# ARM_EURO_Platine5.net
KiCad netlist of a schematic drawn in Altium Designer
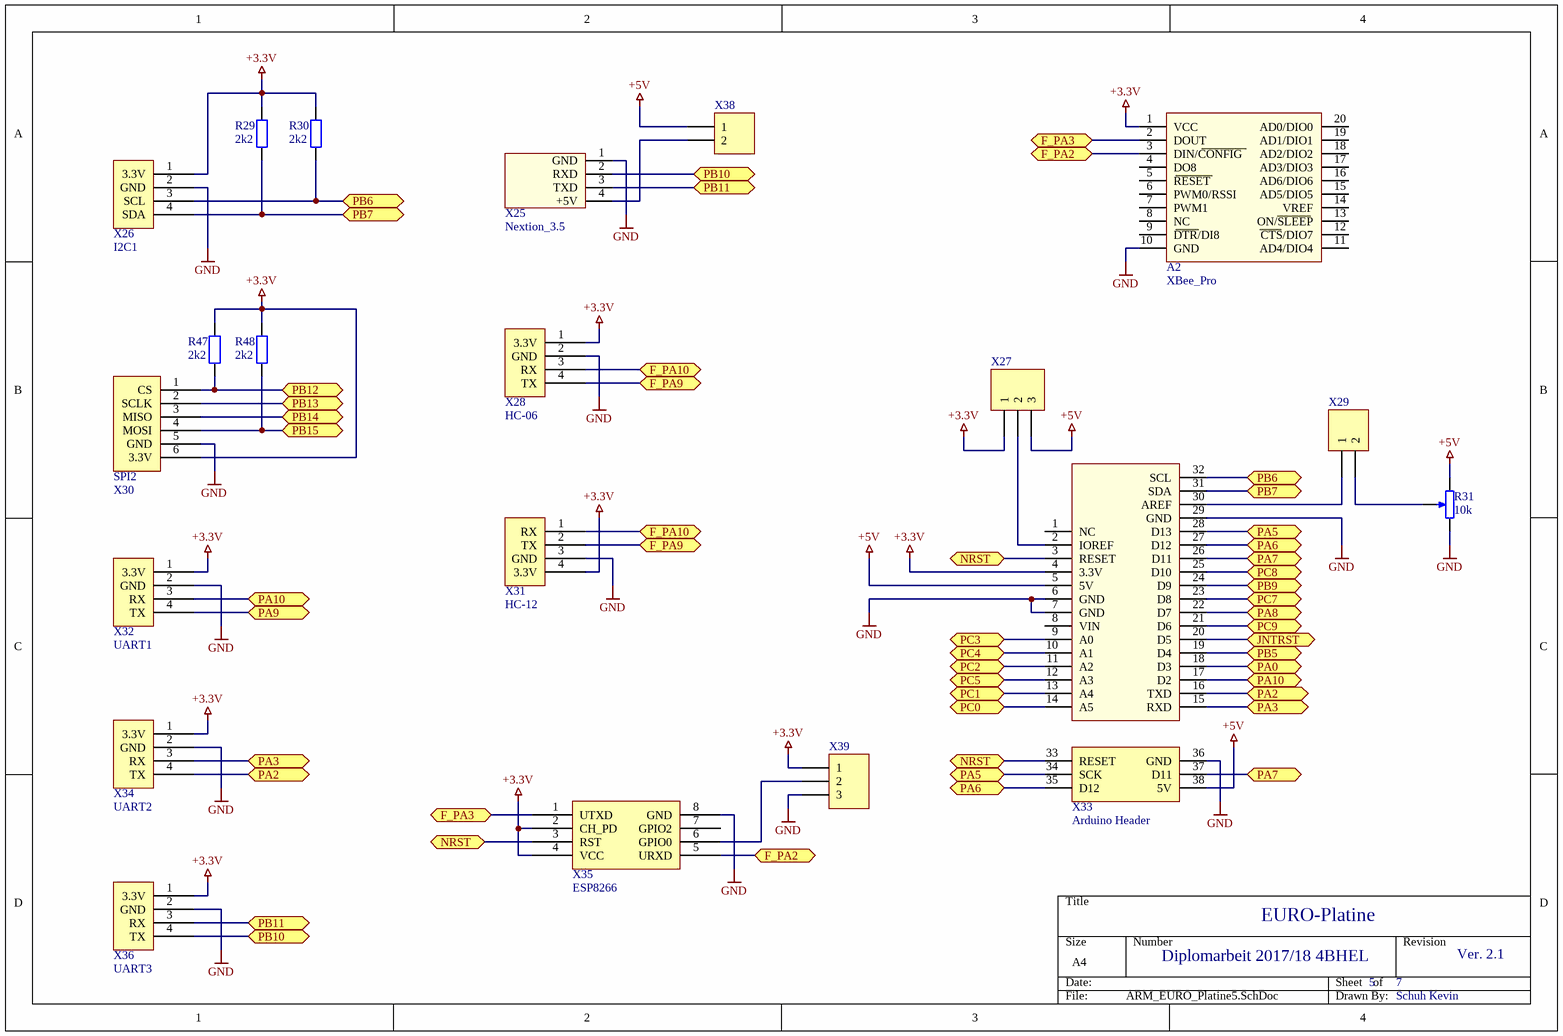
[diagram p0: ARM_EURO_Platine5.SchDoc]

(export (version "E")
  (design (tool "Eeschema 10.0.6"))
  (components
    (comp (ref "A2")
      (value "XBee_Pro")
      (footprint "XBee_Pro")
      (description "Funkmodul")
      (libsource (lib "ARM_Libary_EURO") (part "XBee_Pro"))
    )
    (comp (ref "R29")
      (value "2k2")
      (footprint "0805_Res")
      (description "Resistor")
      (fields (field (name "Comment") "Res_SMD") (field (name "PUBLISHER") "Altium Limited"))
      (libsource (lib "ARM_Libary_EURO") (part "Res_SMD"))
    )
    (comp (ref "R30")
      (value "2k2")
      (footprint "0805_Res")
      (description "Resistor")
      (fields (field (name "Comment") "Res_SMD") (field (name "PUBLISHER") "Altium Limited"))
      (libsource (lib "ARM_Libary_EURO") (part "Res_SMD"))
    )
    (comp (ref "R31")
      (value "10k")
      (footprint "Potentiometer")
      (description "Potentiometer")
      (fields (field (name "Comment") "RPot") (field (name "PUBLISHER") "Altium Limited"))
      (libsource (lib "ARM_Libary_EURO") (part "RPot"))
    )
    (comp (ref "R47")
      (value "2k2")
      (footprint "0805_Res")
      (description "Resistor")
      (fields (field (name "Comment") "Res_SMD") (field (name "PUBLISHER") "Altium Limited"))
      (libsource (lib "ARM_Libary_EURO") (part "Res_SMD"))
    )
    (comp (ref "R48")
      (value "2k2")
      (footprint "0805_Res")
      (description "Resistor")
      (fields (field (name "Comment") "Res_SMD") (field (name "PUBLISHER") "Altium Limited"))
      (libsource (lib "ARM_Libary_EURO") (part "Res_SMD"))
    )
    (comp (ref "X25")
      (value "Nextion_3.5")
      (footprint "Nextion_3.5")
      (libsource (lib "ARM_Libary_EURO") (part "Nextion_3.5"))
    )
    (comp (ref "X26")
      (value "I2C1")
      (footprint "I2C_Interface")
      (description "Stiftleiste 4Pol")
      (libsource (lib "ARM_Libary_EURO") (part "I2C_Interface"))
    )
    (comp (ref "X27")
      (value "Header_3")
      (footprint "HDR1X3")
      (description "Header, 3-Pin")
      (fields (field (name "PUBLISHER") "Altium Limited"))
      (libsource (lib "ARM_Libary_EURO") (part "Header_3"))
    )
    (comp (ref "X28")
      (value "HC-06")
      (footprint "HC_06")
      (description "Stiftleiste 4Pol")
      (libsource (lib "ARM_Libary_EURO") (part "HC_06"))
    )
    (comp (ref "X29")
      (value "Header")
      (footprint "HDR1X2")
      (description "Header, 2-Pin")
      (fields (field (name "PUBLISHER") "Altium Limited"))
      (libsource (lib "") (part "Header_2_1"))
    )
    (comp (ref "X30")
      (value "SPI2")
      (footprint "SPI_Interface")
      (description "Stiftleiste 6Pol")
      (libsource (lib "ARM_Libary_EURO") (part "SPI_Interface"))
    )
    (comp (ref "X31") (value "HC-12") (footprint "HC_12") (libsource (lib "ARM_Libary_EURO") (part "HC_12")))
    (comp (ref "X32")
      (value "UART1")
      (footprint "UART_Interface")
      (description "Stiftleiste 4Pol")
      (libsource (lib "ARM_Libary_EURO") (part "UART_Interface"))
    )
    (comp (ref "X33")
      (value "Arduino Header")
      (footprint "Arduino")
      (libsource (lib "ARM_Libary_EURO") (part "Arduino"))
    )
    (comp (ref "X34")
      (value "UART2")
      (footprint "UART_Interface")
      (description "Stiftleiste 4Pol")
      (libsource (lib "ARM_Libary_EURO") (part "UART_Interface"))
    )
    (comp (ref "X35")
      (value "ESP8266")
      (footprint "ESP8266")
      (description "W-LAN Modul")
      (libsource (lib "ARM_Libary_EURO") (part "ESP8266"))
    )
    (comp (ref "X36")
      (value "UART3")
      (footprint "UART_Interface")
      (description "Stiftleiste 4Pol")
      (libsource (lib "ARM_Libary_EURO") (part "UART_Interface"))
    )
    (comp (ref "X38")
      (value "Header")
      (footprint "HDR1X2")
      (description "Header, 2-Pin")
      (fields (field (name "PUBLISHER") "Altium Limited"))
      (libsource (lib "ARM_Libary_EURO") (part "Header_2"))
    )
    (comp (ref "X39")
      (value "Header_3")
      (footprint "HDR1X3")
      (description "Header, 3-Pin")
      (fields (field (name "PUBLISHER") "Altium Limited"))
      (libsource (lib "") (part "Header_3_1"))
    )
  )
  (nets
    (net (code "1") (name "+3.3V") (class "Default")
      (node (ref "A2") (pin "1") (pinfunction "VCC_1") (pintype "passive"))
      (node (ref "R29") (pin "2") (pinfunction "2_2") (pintype "passive"))
      (node (ref "R30") (pin "2") (pinfunction "2_2") (pintype "passive"))
      (node (ref "R47") (pin "2") (pinfunction "2_2") (pintype "passive"))
      (node (ref "R48") (pin "2") (pinfunction "2_2") (pintype "passive"))
      (node (ref "X26") (pin "1") (pinfunction "3.3V_1") (pintype "passive"))
      (node (ref "X27") (pin "1") (pinfunction "1_1") (pintype "passive"))
      (node (ref "X28") (pin "1") (pinfunction "3.3V_1") (pintype "passive"))
      (node (ref "X30") (pin "6") (pinfunction "3.3V_6") (pintype "passive"))
      (node (ref "X31") (pin "4") (pinfunction "3.3V_4") (pintype "passive"))
      (node (ref "X32") (pin "1") (pinfunction "3.3V_1") (pintype "passive"))
      (node (ref "X33") (pin "4") (pinfunction "3.3V_4") (pintype "passive"))
      (node (ref "X34") (pin "1") (pinfunction "3.3V_1") (pintype "passive"))
      (node (ref "X35") (pin "2") (pinfunction "CH_PD_2") (pintype "passive"))
      (node (ref "X35") (pin "4") (pinfunction "VCC_4") (pintype "passive"))
      (node (ref "X36") (pin "1") (pinfunction "3.3V_1") (pintype "passive"))
      (node (ref "X39") (pin "1") (pinfunction "1_1") (pintype "passive"))
    )
    (net (code "2") (name "+5V") (class "Default")
      (node (ref "R31") (pin "1") (pinfunction "TOP_1") (pintype "passive"))
      (node (ref "X27") (pin "3") (pinfunction "3_3") (pintype "passive"))
      (node (ref "X33") (pin "38") (pinfunction "5V_38") (pintype "passive"))
      (node (ref "X33") (pin "5") (pinfunction "5V_5") (pintype "passive"))
      (node (ref "X38") (pin "1") (pinfunction "1_1") (pintype "passive"))
    )
    (net (code "3") (name "/F_PA2") (class "Default")
      (node (ref "A2") (pin "3") (pinfunction "DIN/CONFIG_3") (pintype "passive"))
      (node (ref "X35") (pin "5") (pinfunction "URXD_5") (pintype "passive"))
    )
    (net (code "4") (name "/F_PA3") (class "Default")
      (node (ref "A2") (pin "2") (pinfunction "DOUT_2") (pintype "passive"))
      (node (ref "X35") (pin "1") (pinfunction "UTXD_1") (pintype "passive"))
    )
    (net (code "5") (name "/F_PA9") (class "Default")
      (node (ref "X28") (pin "4") (pinfunction "TX_4") (pintype "passive"))
      (node (ref "X31") (pin "2") (pinfunction "TX_2") (pintype "passive"))
    )
    (net (code "6") (name "/F_PA10") (class "Default")
      (node (ref "X28") (pin "3") (pinfunction "RX_3") (pintype "passive"))
      (node (ref "X31") (pin "1") (pinfunction "RX_1") (pintype "passive"))
    )
    (net (code "7") (name "/JNTRST") (class "Default")
      (node (ref "X33") (pin "20") (pinfunction "D5_20") (pintype "passive"))
    )
    (net (code "8") (name "/NRST") (class "Default")
      (node (ref "X33") (pin "3") (pinfunction "RESET_3") (pintype "passive"))
      (node (ref "X33") (pin "33") (pinfunction "RESET_33") (pintype "passive"))
      (node (ref "X35") (pin "3") (pinfunction "RST_3") (pintype "passive"))
    )
    (net (code "9") (name "/PA0") (class "Default")
      (node (ref "X33") (pin "18") (pinfunction "D3_18") (pintype "passive"))
    )
    (net (code "10") (name "/PA2") (class "Default")
      (node (ref "X33") (pin "16") (pinfunction "TXD_16") (pintype "passive"))
      (node (ref "X34") (pin "4") (pinfunction "TX_4") (pintype "passive"))
    )
    (net (code "11") (name "/PA3") (class "Default")
      (node (ref "X33") (pin "15") (pinfunction "RXD_15") (pintype "passive"))
      (node (ref "X34") (pin "3") (pinfunction "RX_3") (pintype "passive"))
    )
    (net (code "12") (name "/PA5") (class "Default")
      (node (ref "X33") (pin "28") (pinfunction "D13_28") (pintype "passive"))
      (node (ref "X33") (pin "34") (pinfunction "SCK_34") (pintype "passive"))
    )
    (net (code "13") (name "/PA6") (class "Default")
      (node (ref "X33") (pin "27") (pinfunction "D12_27") (pintype "passive"))
      (node (ref "X33") (pin "35") (pinfunction "D12_35") (pintype "passive"))
    )
    (net (code "14") (name "/PA7") (class "Default")
      (node (ref "X33") (pin "26") (pinfunction "D11_26") (pintype "passive"))
      (node (ref "X33") (pin "37") (pinfunction "D11_37") (pintype "passive"))
    )
    (net (code "15") (name "/PA8") (class "Default")
      (node (ref "X33") (pin "22") (pinfunction "D7_22") (pintype "passive"))
    )
    (net (code "16") (name "/PA9") (class "Default")
      (node (ref "X32") (pin "4") (pinfunction "TX_4") (pintype "passive"))
    )
    (net (code "17") (name "/PA10") (class "Default")
      (node (ref "X32") (pin "3") (pinfunction "RX_3") (pintype "passive"))
      (node (ref "X33") (pin "17") (pinfunction "D2_17") (pintype "passive"))
    )
    (net (code "18") (name "/PB5") (class "Default")
      (node (ref "X33") (pin "19") (pinfunction "D4_19") (pintype "passive"))
    )
    (net (code "19") (name "/PB6") (class "Default")
      (node (ref "R30") (pin "1") (pinfunction "1_1") (pintype "passive"))
      (node (ref "X26") (pin "3") (pinfunction "SCL_3") (pintype "passive"))
      (node (ref "X33") (pin "32") (pinfunction "SCL_32") (pintype "passive"))
    )
    (net (code "20") (name "/PB7") (class "Default")
      (node (ref "R29") (pin "1") (pinfunction "1_1") (pintype "passive"))
      (node (ref "X26") (pin "4") (pinfunction "SDA_4") (pintype "passive"))
      (node (ref "X33") (pin "31") (pinfunction "SDA_31") (pintype "passive"))
    )
    (net (code "21") (name "/PB9") (class "Default")
      (node (ref "X33") (pin "24") (pinfunction "D9_24") (pintype "passive"))
    )
    (net (code "22") (name "/PB10") (class "Default")
      (node (ref "X25") (pin "2") (pinfunction "RXD_2") (pintype "passive"))
      (node (ref "X36") (pin "4") (pinfunction "TX_4") (pintype "passive"))
    )
    (net (code "23") (name "/PB11") (class "Default")
      (node (ref "X25") (pin "3") (pinfunction "TXD_3") (pintype "passive"))
      (node (ref "X36") (pin "3") (pinfunction "RX_3") (pintype "passive"))
    )
    (net (code "24") (name "/PB12") (class "Default")
      (node (ref "R47") (pin "1") (pinfunction "1_1") (pintype "passive"))
      (node (ref "X30") (pin "1") (pinfunction "CS_1") (pintype "passive"))
    )
    (net (code "25") (name "/PB13") (class "Default")
      (node (ref "X30") (pin "2") (pinfunction "SCLK_2") (pintype "passive"))
    )
    (net (code "26") (name "/PB14") (class "Default")
      (node (ref "X30") (pin "3") (pinfunction "MISO_3") (pintype "passive"))
    )
    (net (code "27") (name "/PB15") (class "Default")
      (node (ref "R48") (pin "1") (pinfunction "1_1") (pintype "passive"))
      (node (ref "X30") (pin "4") (pinfunction "MOSI_4") (pintype "passive"))
    )
    (net (code "28") (name "/PC0") (class "Default")
      (node (ref "X33") (pin "14") (pinfunction "A5_14") (pintype "passive"))
    )
    (net (code "29") (name "/PC1") (class "Default")
      (node (ref "X33") (pin "13") (pinfunction "A4_13") (pintype "passive"))
    )
    (net (code "30") (name "/PC2") (class "Default")
      (node (ref "X33") (pin "11") (pinfunction "A2_11") (pintype "passive"))
    )
    (net (code "31") (name "/PC3") (class "Default")
      (node (ref "X33") (pin "9") (pinfunction "A0_9") (pintype "passive"))
    )
    (net (code "32") (name "/PC4") (class "Default")
      (node (ref "X33") (pin "10") (pinfunction "A1_10") (pintype "passive"))
    )
    (net (code "33") (name "/PC5") (class "Default")
      (node (ref "X33") (pin "12") (pinfunction "A3_12") (pintype "passive"))
    )
    (net (code "34") (name "/PC7") (class "Default")
      (node (ref "X33") (pin "23") (pinfunction "D8_23") (pintype "passive"))
    )
    (net (code "35") (name "/PC8") (class "Default")
      (node (ref "X33") (pin "25") (pinfunction "D10_25") (pintype "passive"))
    )
    (net (code "36") (name "/PC9") (class "Default")
      (node (ref "X33") (pin "21") (pinfunction "D6_21") (pintype "passive"))
    )
    (net (code "37") (name "GND") (class "Default")
      (node (ref "A2") (pin "10") (pinfunction "GND_10") (pintype "passive"))
      (node (ref "R31") (pin "2") (pinfunction "BOT_2") (pintype "passive"))
      (node (ref "X25") (pin "1") (pinfunction "GND_1") (pintype "passive"))
      (node (ref "X26") (pin "2") (pinfunction "GND_2") (pintype "passive"))
      (node (ref "X28") (pin "2") (pinfunction "GND_2") (pintype "passive"))
      (node (ref "X30") (pin "5") (pinfunction "GND_5") (pintype "passive"))
      (node (ref "X31") (pin "3") (pinfunction "GND_3") (pintype "passive"))
      (node (ref "X32") (pin "2") (pinfunction "GND_2") (pintype "passive"))
      (node (ref "X33") (pin "29") (pinfunction "GND_29") (pintype "passive"))
      (node (ref "X33") (pin "36") (pinfunction "GND_36") (pintype "passive"))
      (node (ref "X33") (pin "6") (pinfunction "GND_6") (pintype "passive"))
      (node (ref "X33") (pin "7") (pinfunction "GND_7") (pintype "passive"))
      (node (ref "X34") (pin "2") (pinfunction "GND_2") (pintype "passive"))
      (node (ref "X35") (pin "8") (pinfunction "GND_8") (pintype "passive"))
      (node (ref "X36") (pin "2") (pinfunction "GND_2") (pintype "passive"))
      (node (ref "X39") (pin "3") (pinfunction "3_3") (pintype "passive"))
    )
    (net (code "38") (name "Net-(R31-TAP)") (class "Default")
      (node (ref "R31") (pin "3") (pinfunction "TAP_3") (pintype "passive"))
      (node (ref "X29") (pin "2") (pinfunction "2_2") (pintype "passive"))
    )
    (net (code "39") (name "Net-(X25-+5V)") (class "Default")
      (node (ref "X25") (pin "4") (pinfunction "+5V_4") (pintype "passive"))
      (node (ref "X38") (pin "2") (pinfunction "2_2") (pintype "passive"))
    )
    (net (code "40") (name "Net-(X33-AREF)") (class "Default")
      (node (ref "X29") (pin "1") (pinfunction "1_1") (pintype "passive"))
      (node (ref "X33") (pin "30") (pinfunction "AREF_30") (pintype "passive"))
    )
    (net (code "41") (name "Net-(X33-IOREF)") (class "Default")
      (node (ref "X27") (pin "2") (pinfunction "2_2") (pintype "passive"))
      (node (ref "X33") (pin "2") (pinfunction "IOREF_2") (pintype "passive"))
    )
    (net (code "42") (name "Net-(X35-GPIO0)") (class "Default")
      (node (ref "X35") (pin "6") (pinfunction "GPIO0_6") (pintype "passive"))
      (node (ref "X39") (pin "2") (pinfunction "2_2") (pintype "passive"))
    )
    (net (code "43") (name "unconnected-(A2-AD0{slash}DIO0-Pad20)") (class "Default")
      (node (ref "A2") (pin "20") (pinfunction "AD0/DIO0_20") (pintype "passive"))
    )
    (net (code "44") (name "unconnected-(A2-AD1{slash}DIO1-Pad19)") (class "Default")
      (node (ref "A2") (pin "19") (pinfunction "AD1/DIO1_19") (pintype "passive"))
    )
    (net (code "45") (name "unconnected-(A2-AD2{slash}DIO2-Pad18)") (class "Default")
      (node (ref "A2") (pin "18") (pinfunction "AD2/DIO2_18") (pintype "passive"))
    )
    (net (code "46") (name "unconnected-(A2-AD3{slash}DIO3-Pad17)") (class "Default")
      (node (ref "A2") (pin "17") (pinfunction "AD3/DIO3_17") (pintype "passive"))
    )
    (net (code "47") (name "unconnected-(A2-AD4{slash}DIO4-Pad11)") (class "Default")
      (node (ref "A2") (pin "11") (pinfunction "AD4/DIO4_11") (pintype "passive"))
    )
    (net (code "48") (name "unconnected-(A2-AD5{slash}DIO5-Pad15)") (class "Default")
      (node (ref "A2") (pin "15") (pinfunction "AD5/DIO5_15") (pintype "passive"))
    )
    (net (code "49") (name "unconnected-(A2-AD6{slash}DIO6-Pad16)") (class "Default")
      (node (ref "A2") (pin "16") (pinfunction "AD6/DIO6_16") (pintype "passive"))
    )
    (net (code "50") (name "unconnected-(A2-CTS{slash}DIO7-Pad12)") (class "Default")
      (node (ref "A2") (pin "12") (pinfunction "CTS/DIO7_12") (pintype "passive"))
    )
    (net (code "51") (name "unconnected-(A2-DO8-Pad4)") (class "Default")
      (node (ref "A2") (pin "4") (pinfunction "DO8_4") (pintype "passive"))
    )
    (net (code "52") (name "unconnected-(A2-DTR{slash}DI8-Pad9)") (class "Default")
      (node (ref "A2") (pin "9") (pinfunction "DTR/DI8_9") (pintype "passive"))
    )
    (net (code "53") (name "unconnected-(A2-NC-Pad8)") (class "Default")
      (node (ref "A2") (pin "8") (pinfunction "NC_8") (pintype "passive"))
    )
    (net (code "54") (name "unconnected-(A2-ON{slash}SLEEP-Pad13)") (class "Default")
      (node (ref "A2") (pin "13") (pinfunction "ON/SLEEP_13") (pintype "passive"))
    )
    (net (code "55") (name "unconnected-(A2-PWM0{slash}RSSI-Pad6)") (class "Default")
      (node (ref "A2") (pin "6") (pinfunction "PWM0/RSSI_6") (pintype "passive"))
    )
    (net (code "56") (name "unconnected-(A2-PWM1-Pad7)") (class "Default")
      (node (ref "A2") (pin "7") (pinfunction "PWM1_7") (pintype "passive"))
    )
    (net (code "57") (name "unconnected-(A2-RESET-Pad5)") (class "Default")
      (node (ref "A2") (pin "5") (pinfunction "RESET_5") (pintype "passive"))
    )
    (net (code "58") (name "unconnected-(A2-VREF-Pad14)") (class "Default")
      (node (ref "A2") (pin "14") (pinfunction "VREF_14") (pintype "passive"))
    )
    (net (code "59") (name "unconnected-(X33-NC-Pad1)") (class "Default")
      (node (ref "X33") (pin "1") (pinfunction "NC_1") (pintype "passive"))
    )
    (net (code "60") (name "unconnected-(X33-VIN-Pad8)") (class "Default")
      (node (ref "X33") (pin "8") (pinfunction "VIN_8") (pintype "passive"))
    )
    (net (code "61") (name "unconnected-(X35-GPIO2-Pad7)") (class "Default")
      (node (ref "X35") (pin "7") (pinfunction "GPIO2_7") (pintype "passive"))
    )
  )
)
